# Power.net
KiCad netlist of a schematic drawn in Altium Designer
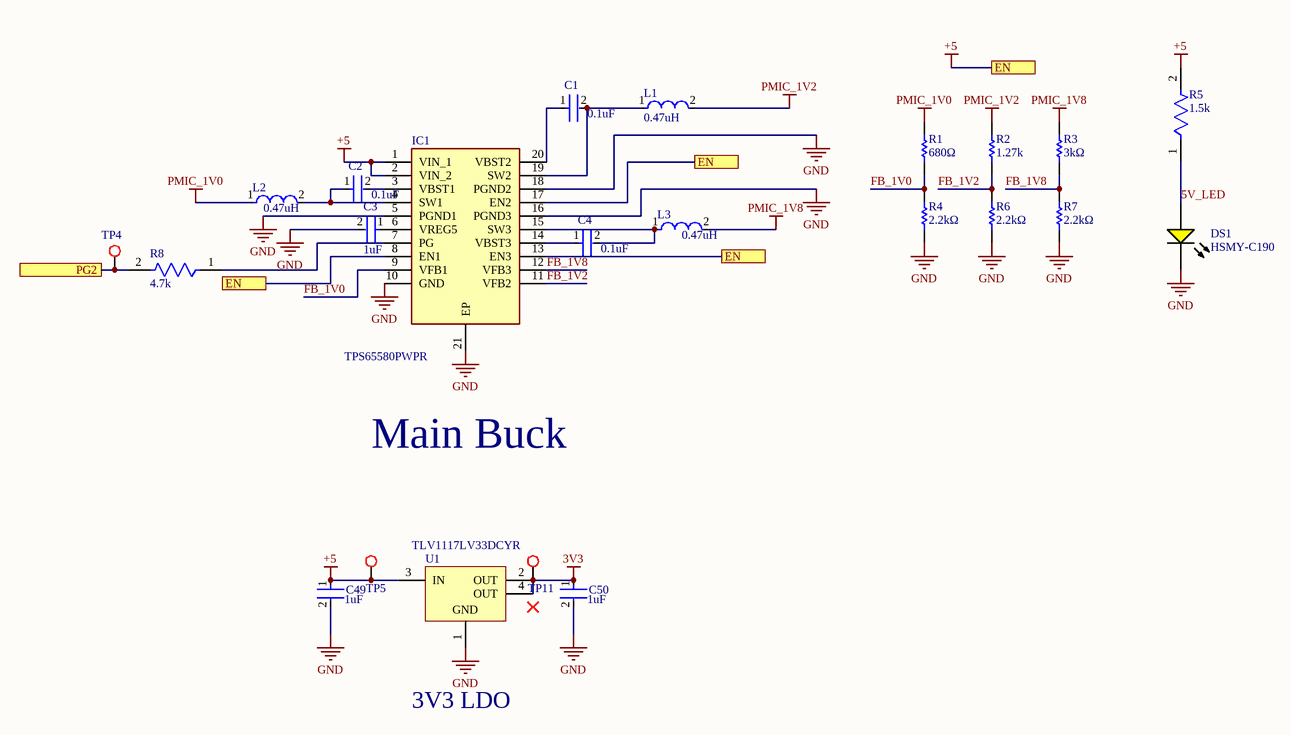
[diagram p0: Power.SchDoc]

(export (version "E")
  (design (tool "Eeschema 10.0.6"))
  (components
    (comp (ref "C1")
      (value "0.1uF")
      (footprint "FP-0603-L_1_6_0_1-W_0_8_0-IPC_C")
      (description "None")
      (fields (field (name "TOLERANCE") "10%"))
      (libsource (lib "Altium Content Vault") (part "02cd4be3c70576c341d710602a673aa"))
    )
    (comp (ref "C2")
      (value "0.1uF")
      (footprint "FP-0603-L_1_6_0_1-W_0_8_0-IPC_C")
      (description "None")
      (fields (field (name "TOLERANCE") "10%"))
      (libsource (lib "Altium Content Vault") (part "02cd4be3c70576c341d710602a673aa"))
    )
    (comp (ref "C3")
      (value "1uF")
      (footprint "FP-CL10-IPC_C")
      (description "Cap Ceramic 1uF 10V X5R ±10% Pad SMD 0603 +85°C T/R")
      (fields (field (name "VOLTAGE") "10V") (field (name "TOLERANCE") "10%"))
      (libsource (lib "Altium Content Vault") (part "b4654b650e69147ec39a6b967a45e02"))
    )
    (comp (ref "C4")
      (value "0.1uF")
      (footprint "FP-0603-L_1_6_0_1-W_0_8_0-IPC_C")
      (description "None")
      (fields (field (name "TOLERANCE") "10%"))
      (libsource (lib "Altium Content Vault") (part "02cd4be3c70576c341d710602a673aa"))
    )
    (comp (ref "C49")
      (value "1uF")
      (footprint "FP-CL10-IPC_C")
      (description "Cap Ceramic 1uF 10V X5R ±10% Pad SMD 0603 +85°C T/R")
      (fields (field (name "VOLTAGE") "10V") (field (name "TOLERANCE") "10%"))
      (libsource (lib "Altium Content Vault") (part "b4654b650e69147ec39a6b967a45e02"))
    )
    (comp (ref "C50")
      (value "1uF")
      (footprint "FP-CL10-IPC_C")
      (description "Cap Ceramic 1uF 10V X5R ±10% Pad SMD 0603 +85°C T/R")
      (fields (field (name "VOLTAGE") "10V") (field (name "TOLERANCE") "10%"))
      (libsource (lib "Altium Content Vault") (part "b4654b650e69147ec39a6b967a45e02"))
    )
    (comp (ref "DS1")
      (value "HSMY-C190")
      (footprint "AVAG-HSMX-C190_V")
      (description "LED Uni-Color Yellow, 65 mW, 20 mA, -40 to 85 degC, 2-Pin SMD, RoHS, Tape and Reel")
      (fields (field (name "TOLERANCE") "1%"))
      (libsource (lib "Altium Content Vault") (part "LED-YELLOW-AK-2"))
    )
    (comp (ref "IC1")
      (value "TPS65580PWPR")
      (footprint "SamacSys:SOP65P640X120-21N")
      (description "Integrated Circuit")
      (fields (field (name "MOUSER PART NUMBER") "595-TPS65580PWPR"))
      (libsource (lib "*") (part "TPS65580PWPR"))
    )
    (comp (ref "L1")
      (value "0.47uH")
      (footprint "FP-IHLP-3232DZ-FP_2_413x5-MFG")
      (description "Commercial Inductors, Low DCR Series 0.47uH 25A 2.38mΩ 20%")
      (fields (field (name "TOLERANCE") "20%"))
      (libsource (lib "Altium Content Vault") (part "725321dda6339637d4d059423bc1c3c"))
    )
    (comp (ref "L2")
      (value "0.47uH")
      (footprint "FP-IHLP-3232DZ-FP_2_413x5-MFG")
      (description "Commercial Inductors, Low DCR Series 0.47uH 25A 2.38mΩ 20%")
      (fields (field (name "TOLERANCE") "20%"))
      (libsource (lib "Altium Content Vault") (part "725321dda6339637d4d059423bc1c3c"))
    )
    (comp (ref "L3")
      (value "0.47uH")
      (footprint "FP-IHLP-3232DZ-FP_2_413x5-MFG")
      (description "Commercial Inductors, Low DCR Series 0.47uH 25A 2.38mΩ 20%")
      (fields (field (name "TOLERANCE") "20%"))
      (libsource (lib "Altium Content Vault") (part "725321dda6339637d4d059423bc1c3c"))
    )
    (comp (ref "R1")
      (value "680Ω")
      (footprint "RESC1608X55X30NL20T10")
      (fields (field (name "MANUFACTURER") "KOA Speer") (field (name "PART NUMBER") "RK73H1JTTD6800F"))
      (libsource (lib "Altium Content Vault") (part "RES"))
    )
    (comp (ref "R2")
      (value "1.27k")
      (footprint "RESC1609X50X30NL10T20")
      (fields (field (name "PART NUMBER") "CRCW06031K27FKEA") (field (name "MANUFACTURER") "Vishay Dale"))
      (libsource (lib "Altium Content Vault") (part "RES"))
    )
    (comp (ref "R3")
      (value "3kΩ")
      (footprint "RESC1608X55X30NL20T10")
      (fields (field (name "MANUFACTURER") "KOA Speer") (field (name "PART NUMBER") "SG73P1JTTD3001F"))
      (libsource (lib "Altium Content Vault") (part "RES"))
    )
    (comp (ref "R4")
      (value "2.2kΩ")
      (footprint "RESC1609X50X30NL10T20")
      (fields (field (name "PART NUMBER") "CRCW06032K20FKEA") (field (name "MANUFACTURER") "Vishay Dale"))
      (libsource (lib "Altium Content Vault") (part "RES"))
    )
    (comp (ref "R5")
      (value "1.5k")
      (footprint "FP-RC1608-IPC_B")
      (description "Res Thick Film 0603 1.5kΩ 1% 0.1W ±100ppm/°C Molded SMD T/R")
      (fields (field (name "TOLERANCE") "1%"))
      (libsource (lib "Altium Content Vault") (part "1029c3af85768c4190bb7ad29bc67b5"))
    )
    (comp (ref "R6")
      (value "2.2kΩ")
      (footprint "RESC1609X50X30NL10T20")
      (fields (field (name "PART NUMBER") "CRCW06032K20FKEA") (field (name "MANUFACTURER") "Vishay Dale"))
      (libsource (lib "Altium Content Vault") (part "RES"))
    )
    (comp (ref "R7")
      (value "2.2kΩ")
      (footprint "RESC1609X50X30NL10T20")
      (fields (field (name "PART NUMBER") "CRCW06032K20FKEA") (field (name "MANUFACTURER") "Vishay Dale"))
      (libsource (lib "Altium Content Vault") (part "RES"))
    )
    (comp (ref "R8")
      (value "4.7k")
      (footprint "FP-CRCW0603-HPe3-IPC_A")
      (description "RES Thick Film, 4.7kΩ, 5%, 0.33W, 200ppm/°C, 0603")
      (fields (field (name "TOLERANCE") "5%"))
      (libsource (lib "Altium Content Vault") (part "1029c3af85768c4190bb7ad29bc67b5"))
    )
    (comp (ref "TP4") (value "TP_1") (footprint "Testpoint") (libsource (lib "Schlib1") (part "Testpoint")))
    (comp (ref "TP5") (value "TP") (footprint "Testpoint") (libsource (lib "Schlib1") (part "Testpoint")))
    (comp (ref "TP11") (value "TP") (footprint "Testpoint") (libsource (lib "Schlib1") (part "Testpoint")))
    (comp (ref "U1")
      (value "TLV1117LV33DCYR")
      (footprint "DCY0004A_N")
      (fields (field (name "MANUFACTURER") "Texas Instruments"))
      (libsource (lib "Altium Content Vault") (part "TI-TLV1117LV33DCY4"))
    )
  )
  (nets
    (net (code "1") (name "+5") (class "Default")
      (node (ref "C49") (pin "1") (pinfunction "1_1") (pintype "passive"))
      (node (ref "IC1") (pin "1") (pinfunction "VIN_1_1") (pintype "passive"))
      (node (ref "IC1") (pin "13") (pinfunction "EN3_13") (pintype "passive"))
      (node (ref "IC1") (pin "17") (pinfunction "EN2_17") (pintype "passive"))
      (node (ref "IC1") (pin "2") (pinfunction "VIN_2_2") (pintype "passive"))
      (node (ref "IC1") (pin "8") (pinfunction "EN1_8") (pintype "passive"))
      (node (ref "R5") (pin "2") (pinfunction "2_2") (pintype "passive"))
      (node (ref "TP5") (pin "0") (pinfunction "0_0") (pintype "passive"))
      (node (ref "U1") (pin "3") (pinfunction "IN_3") (pintype "power_in"))
    )
    (net (code "2") (name "/5V_LED") (class "Default")
      (node (ref "DS1") (pin "1") (pinfunction "A_1") (pintype "passive"))
      (node (ref "R5") (pin "1") (pinfunction "1_1") (pintype "passive"))
    )
    (net (code "3") (name "/FB_1V0") (class "Default")
      (node (ref "IC1") (pin "9") (pinfunction "VFB1_9") (pintype "passive"))
      (node (ref "R1") (pin "1") (pinfunction "1_1") (pintype "passive"))
      (node (ref "R4") (pin "2") (pinfunction "2_2") (pintype "passive"))
    )
    (net (code "4") (name "/FB_1V2") (class "Default")
      (node (ref "IC1") (pin "11") (pinfunction "VFB2_11") (pintype "passive"))
      (node (ref "R2") (pin "1") (pinfunction "1_1") (pintype "passive"))
      (node (ref "R6") (pin "2") (pinfunction "2_2") (pintype "passive"))
    )
    (net (code "5") (name "/FB_1V8") (class "Default")
      (node (ref "IC1") (pin "12") (pinfunction "VFB3_12") (pintype "passive"))
      (node (ref "R3") (pin "1") (pinfunction "1_1") (pintype "passive"))
      (node (ref "R7") (pin "2") (pinfunction "2_2") (pintype "passive"))
    )
    (net (code "6") (name "/PG2") (class "Default")
      (node (ref "R8") (pin "2") (pinfunction "2_2") (pintype "passive"))
      (node (ref "TP4") (pin "0") (pinfunction "0_0") (pintype "passive"))
    )
    (net (code "7") (name "3V3") (class "Default")
      (node (ref "C50") (pin "1") (pinfunction "1_1") (pintype "passive"))
      (node (ref "TP11") (pin "0") (pinfunction "0_0") (pintype "passive"))
      (node (ref "U1") (pin "2") (pinfunction "OUT_2") (pintype "power_in"))
      (node (ref "U1") (pin "4") (pinfunction "OUT_4") (pintype "power_in"))
    )
    (net (code "8") (name "GND") (class "Default")
      (node (ref "C3") (pin "2") (pinfunction "2_2") (pintype "passive"))
      (node (ref "C49") (pin "2") (pinfunction "2_2") (pintype "passive"))
      (node (ref "C50") (pin "2") (pinfunction "2_2") (pintype "passive"))
      (node (ref "DS1") (pin "2") (pinfunction "K_2") (pintype "passive"))
      (node (ref "IC1") (pin "10") (pinfunction "GND_10") (pintype "passive"))
      (node (ref "IC1") (pin "16") (pinfunction "PGND3_16") (pintype "passive"))
      (node (ref "IC1") (pin "18") (pinfunction "PGND2_18") (pintype "passive"))
      (node (ref "IC1") (pin "21") (pinfunction "EP_21") (pintype "passive"))
      (node (ref "IC1") (pin "5") (pinfunction "PGND1_5") (pintype "passive"))
      (node (ref "R4") (pin "1") (pinfunction "1_1") (pintype "passive"))
      (node (ref "R6") (pin "1") (pinfunction "1_1") (pintype "passive"))
      (node (ref "R7") (pin "1") (pinfunction "1_1") (pintype "passive"))
      (node (ref "U1") (pin "1") (pinfunction "GND_1") (pintype "power_in"))
    )
    (net (code "9") (name "Net-(IC1-PG)") (class "Default")
      (node (ref "IC1") (pin "7") (pinfunction "PG_7") (pintype "passive"))
      (node (ref "R8") (pin "1") (pinfunction "1_1") (pintype "passive"))
    )
    (net (code "10") (name "Net-(IC1-SW1)") (class "Default")
      (node (ref "C2") (pin "1") (pinfunction "1_1") (pintype "passive"))
      (node (ref "IC1") (pin "4") (pinfunction "SW1_4") (pintype "passive"))
      (node (ref "L2") (pin "2") (pinfunction "2_2") (pintype "passive"))
    )
    (net (code "11") (name "Net-(IC1-SW2)") (class "Default")
      (node (ref "C1") (pin "2") (pinfunction "2_2") (pintype "passive"))
      (node (ref "IC1") (pin "19") (pinfunction "SW2_19") (pintype "passive"))
      (node (ref "L1") (pin "1") (pinfunction "1_1") (pintype "passive"))
    )
    (net (code "12") (name "Net-(IC1-SW3)") (class "Default")
      (node (ref "C4") (pin "2") (pinfunction "2_2") (pintype "passive"))
      (node (ref "IC1") (pin "15") (pinfunction "SW3_15") (pintype "passive"))
      (node (ref "L3") (pin "1") (pinfunction "1_1") (pintype "passive"))
    )
    (net (code "13") (name "Net-(IC1-VBST1)") (class "Default")
      (node (ref "C2") (pin "2") (pinfunction "2_2") (pintype "passive"))
      (node (ref "IC1") (pin "3") (pinfunction "VBST1_3") (pintype "passive"))
    )
    (net (code "14") (name "Net-(IC1-VBST2)") (class "Default")
      (node (ref "C1") (pin "1") (pinfunction "1_1") (pintype "passive"))
      (node (ref "IC1") (pin "20") (pinfunction "VBST2_20") (pintype "passive"))
    )
    (net (code "15") (name "Net-(IC1-VBST3)") (class "Default")
      (node (ref "C4") (pin "1") (pinfunction "1_1") (pintype "passive"))
      (node (ref "IC1") (pin "14") (pinfunction "VBST3_14") (pintype "passive"))
    )
    (net (code "16") (name "Net-(IC1-VREG5)") (class "Default")
      (node (ref "C3") (pin "1") (pinfunction "1_1") (pintype "passive"))
      (node (ref "IC1") (pin "6") (pinfunction "VREG5_6") (pintype "passive"))
    )
    (net (code "17") (name "PMIC_1V0") (class "Default")
      (node (ref "L2") (pin "1") (pinfunction "1_1") (pintype "passive"))
      (node (ref "R1") (pin "2") (pinfunction "2_2") (pintype "passive"))
    )
    (net (code "18") (name "PMIC_1V2") (class "Default")
      (node (ref "L1") (pin "2") (pinfunction "2_2") (pintype "passive"))
      (node (ref "R2") (pin "2") (pinfunction "2_2") (pintype "passive"))
    )
    (net (code "19") (name "PMIC_1V8") (class "Default")
      (node (ref "L3") (pin "2") (pinfunction "2_2") (pintype "passive"))
      (node (ref "R3") (pin "2") (pinfunction "2_2") (pintype "passive"))
    )
  )
)
